# buck_connector-2.net
KiCad netlist of a schematic drawn in EAGLE
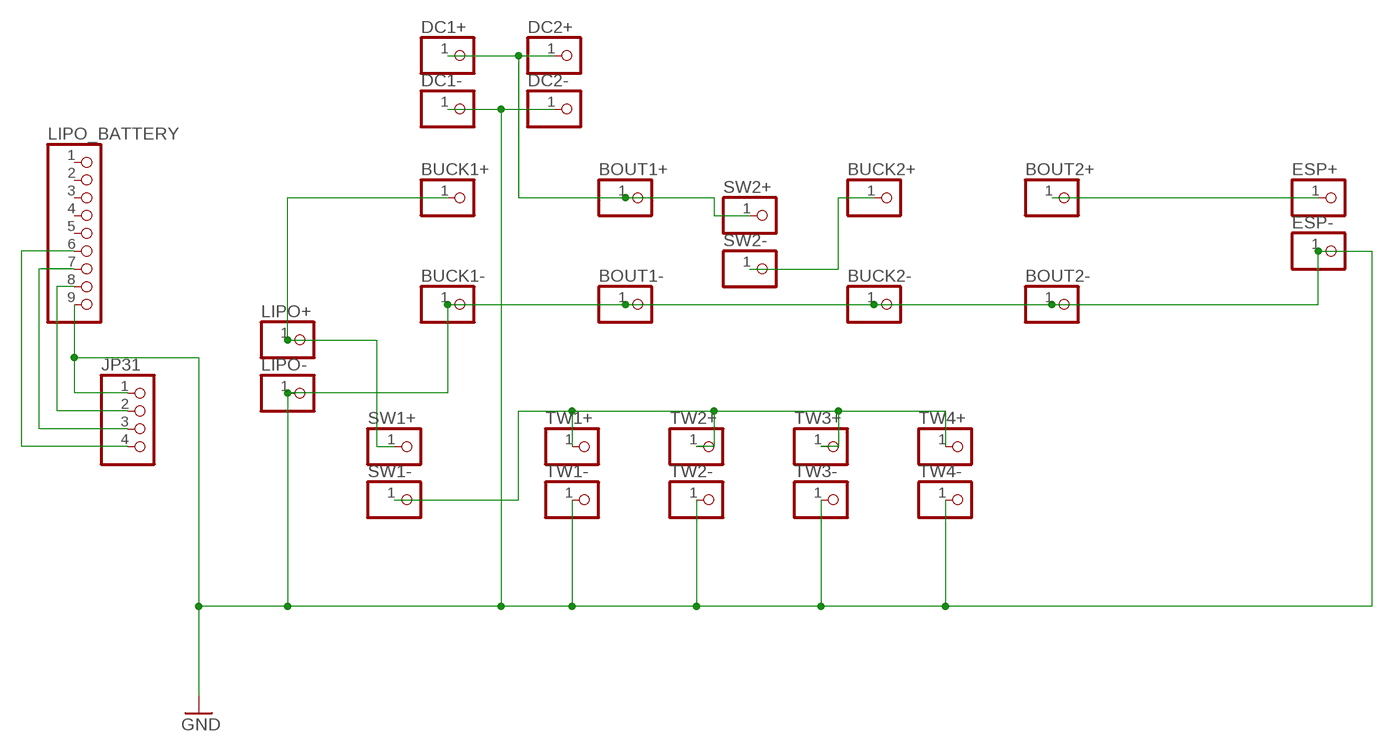
[diagram p0: schematic, sheet 1]

(export (version "E")
  (design (tool "Eeschema 10.0.6"))
  (components
    (comp (ref "BOUT1+")
      (value "PINHD-1X1")
      (footprint "eagle-import:1X01")
      (libsource (lib "eagle-import") (part "PINHD-1X1"))
    )
    (comp (ref "BOUT1-")
      (value "PINHD-1X1")
      (footprint "eagle-import:1X01")
      (libsource (lib "eagle-import") (part "PINHD-1X1"))
    )
    (comp (ref "BOUT2+")
      (value "PINHD-1X1")
      (footprint "eagle-import:1X01")
      (libsource (lib "eagle-import") (part "PINHD-1X1"))
    )
    (comp (ref "BOUT2-")
      (value "PINHD-1X1")
      (footprint "eagle-import:1X01")
      (libsource (lib "eagle-import") (part "PINHD-1X1"))
    )
    (comp (ref "BUCK1+")
      (value "PINHD-1X1")
      (footprint "eagle-import:1X01")
      (libsource (lib "eagle-import") (part "PINHD-1X1"))
    )
    (comp (ref "BUCK1-")
      (value "PINHD-1X1")
      (footprint "eagle-import:1X01")
      (libsource (lib "eagle-import") (part "PINHD-1X1"))
    )
    (comp (ref "BUCK2+")
      (value "PINHD-1X1")
      (footprint "eagle-import:1X01")
      (libsource (lib "eagle-import") (part "PINHD-1X1"))
    )
    (comp (ref "BUCK2-")
      (value "PINHD-1X1")
      (footprint "eagle-import:1X01")
      (libsource (lib "eagle-import") (part "PINHD-1X1"))
    )
    (comp (ref "DC1+")
      (value "PINHD-1X1")
      (footprint "eagle-import:1X01")
      (libsource (lib "eagle-import") (part "PINHD-1X1"))
    )
    (comp (ref "DC1-")
      (value "PINHD-1X1")
      (footprint "eagle-import:1X01")
      (libsource (lib "eagle-import") (part "PINHD-1X1"))
    )
    (comp (ref "DC2+")
      (value "PINHD-1X1")
      (footprint "eagle-import:1X01")
      (libsource (lib "eagle-import") (part "PINHD-1X1"))
    )
    (comp (ref "DC2-")
      (value "PINHD-1X1")
      (footprint "eagle-import:1X01")
      (libsource (lib "eagle-import") (part "PINHD-1X1"))
    )
    (comp (ref "ESP+")
      (value "PINHD-1X1")
      (footprint "eagle-import:1X01")
      (libsource (lib "eagle-import") (part "PINHD-1X1"))
    )
    (comp (ref "ESP-")
      (value "PINHD-1X1")
      (footprint "eagle-import:1X01")
      (libsource (lib "eagle-import") (part "PINHD-1X1"))
    )
    (comp (ref "JP31")
      (value "PINHD-1X4")
      (footprint "eagle-import:1X04")
      (libsource (lib "eagle-import") (part "PINHD-1X4"))
    )
    (comp (ref "LIPO+")
      (value "PINHD-1X1")
      (footprint "eagle-import:1X01")
      (libsource (lib "eagle-import") (part "PINHD-1X1"))
    )
    (comp (ref "LIPO-")
      (value "PINHD-1X1")
      (footprint "eagle-import:1X01")
      (libsource (lib "eagle-import") (part "PINHD-1X1"))
    )
    (comp (ref "LIPO_BATTERY")
      (value "PINHD-1X9")
      (footprint "eagle-import:1X09")
      (libsource (lib "eagle-import") (part "PINHD-1X9"))
    )
    (comp (ref "SW1+")
      (value "PINHD-1X1")
      (footprint "eagle-import:1X01")
      (libsource (lib "eagle-import") (part "PINHD-1X1"))
    )
    (comp (ref "SW1-")
      (value "PINHD-1X1")
      (footprint "eagle-import:1X01")
      (libsource (lib "eagle-import") (part "PINHD-1X1"))
    )
    (comp (ref "SW2+")
      (value "PINHD-1X1")
      (footprint "eagle-import:1X01")
      (libsource (lib "eagle-import") (part "PINHD-1X1"))
    )
    (comp (ref "SW2-")
      (value "PINHD-1X1")
      (footprint "eagle-import:1X01")
      (libsource (lib "eagle-import") (part "PINHD-1X1"))
    )
    (comp (ref "TW1+")
      (value "PINHD-1X1")
      (footprint "eagle-import:1X01")
      (libsource (lib "eagle-import") (part "PINHD-1X1"))
    )
    (comp (ref "TW1-")
      (value "PINHD-1X1")
      (footprint "eagle-import:1X01")
      (libsource (lib "eagle-import") (part "PINHD-1X1"))
    )
    (comp (ref "TW2+")
      (value "PINHD-1X1")
      (footprint "eagle-import:1X01")
      (libsource (lib "eagle-import") (part "PINHD-1X1"))
    )
    (comp (ref "TW2-")
      (value "PINHD-1X1")
      (footprint "eagle-import:1X01")
      (libsource (lib "eagle-import") (part "PINHD-1X1"))
    )
    (comp (ref "TW3+")
      (value "PINHD-1X1")
      (footprint "eagle-import:1X01")
      (libsource (lib "eagle-import") (part "PINHD-1X1"))
    )
    (comp (ref "TW3-")
      (value "PINHD-1X1")
      (footprint "eagle-import:1X01")
      (libsource (lib "eagle-import") (part "PINHD-1X1"))
    )
    (comp (ref "TW4+")
      (value "PINHD-1X1")
      (footprint "eagle-import:1X01")
      (libsource (lib "eagle-import") (part "PINHD-1X1"))
    )
    (comp (ref "TW4-")
      (value "PINHD-1X1")
      (footprint "eagle-import:1X01")
      (libsource (lib "eagle-import") (part "PINHD-1X1"))
    )
  )
  (nets
    (net (code "1") (name "GND") (class "Default")
      (node (ref "BOUT1-") (pin "1") (pinfunction "1_1") (pintype "passive"))
      (node (ref "BOUT2-") (pin "1") (pinfunction "1_1") (pintype "passive"))
      (node (ref "BUCK1-") (pin "1") (pinfunction "1_1") (pintype "passive"))
      (node (ref "BUCK2-") (pin "1") (pinfunction "1_1") (pintype "passive"))
      (node (ref "DC1-") (pin "1") (pinfunction "1_1") (pintype "passive"))
      (node (ref "DC2-") (pin "1") (pinfunction "1_1") (pintype "passive"))
      (node (ref "ESP-") (pin "1") (pinfunction "1_1") (pintype "passive"))
      (node (ref "JP31") (pin "1") (pinfunction "1_1") (pintype "passive"))
      (node (ref "LIPO-") (pin "1") (pinfunction "1_1") (pintype "passive"))
      (node (ref "LIPO_BATTERY") (pin "9") (pinfunction "9_9") (pintype "passive"))
      (node (ref "TW1-") (pin "1") (pinfunction "1_1") (pintype "passive"))
      (node (ref "TW2-") (pin "1") (pinfunction "1_1") (pintype "passive"))
      (node (ref "TW3-") (pin "1") (pinfunction "1_1") (pintype "passive"))
      (node (ref "TW4-") (pin "1") (pinfunction "1_1") (pintype "passive"))
    )
    (net (code "2") (name "Net-(BOUT1+-Pad1)") (class "Default")
      (node (ref "BOUT1+") (pin "1") (pinfunction "1_1") (pintype "passive"))
      (node (ref "DC1+") (pin "1") (pinfunction "1_1") (pintype "passive"))
      (node (ref "DC2+") (pin "1") (pinfunction "1_1") (pintype "passive"))
      (node (ref "SW2+") (pin "1") (pinfunction "1_1") (pintype "passive"))
    )
    (net (code "3") (name "Net-(BOUT2+-Pad1)") (class "Default")
      (node (ref "BOUT2+") (pin "1") (pinfunction "1_1") (pintype "passive"))
      (node (ref "ESP+") (pin "1") (pinfunction "1_1") (pintype "passive"))
    )
    (net (code "4") (name "Net-(BUCK1+-Pad1)") (class "Default")
      (node (ref "BUCK1+") (pin "1") (pinfunction "1_1") (pintype "passive"))
      (node (ref "LIPO+") (pin "1") (pinfunction "1_1") (pintype "passive"))
      (node (ref "SW1+") (pin "1") (pinfunction "1_1") (pintype "passive"))
    )
    (net (code "5") (name "Net-(BUCK2+-Pad1)") (class "Default")
      (node (ref "BUCK2+") (pin "1") (pinfunction "1_1") (pintype "passive"))
      (node (ref "SW2-") (pin "1") (pinfunction "1_1") (pintype "passive"))
    )
    (net (code "6") (name "Net-(JP31-Pad2)") (class "Default")
      (node (ref "JP31") (pin "2") (pinfunction "2_2") (pintype "passive"))
      (node (ref "LIPO_BATTERY") (pin "8") (pinfunction "8_8") (pintype "passive"))
    )
    (net (code "7") (name "Net-(JP31-Pad3)") (class "Default")
      (node (ref "JP31") (pin "3") (pinfunction "3_3") (pintype "passive"))
      (node (ref "LIPO_BATTERY") (pin "7") (pinfunction "7_7") (pintype "passive"))
    )
    (net (code "8") (name "Net-(JP31-Pad4)") (class "Default")
      (node (ref "JP31") (pin "4") (pinfunction "4_4") (pintype "passive"))
      (node (ref "LIPO_BATTERY") (pin "6") (pinfunction "6_6") (pintype "passive"))
    )
    (net (code "9") (name "Net-(SW1--Pad1)") (class "Default")
      (node (ref "SW1-") (pin "1") (pinfunction "1_1") (pintype "passive"))
      (node (ref "TW1+") (pin "1") (pinfunction "1_1") (pintype "passive"))
      (node (ref "TW2+") (pin "1") (pinfunction "1_1") (pintype "passive"))
      (node (ref "TW3+") (pin "1") (pinfunction "1_1") (pintype "passive"))
      (node (ref "TW4+") (pin "1") (pinfunction "1_1") (pintype "passive"))
    )
    (net (code "10") (name "unconnected-(LIPO_BATTERY-Pad1)") (class "Default")
      (node (ref "LIPO_BATTERY") (pin "1") (pinfunction "1_1") (pintype "passive"))
    )
    (net (code "11") (name "unconnected-(LIPO_BATTERY-Pad2)") (class "Default")
      (node (ref "LIPO_BATTERY") (pin "2") (pinfunction "2_2") (pintype "passive"))
    )
    (net (code "12") (name "unconnected-(LIPO_BATTERY-Pad3)") (class "Default")
      (node (ref "LIPO_BATTERY") (pin "3") (pinfunction "3_3") (pintype "passive"))
    )
    (net (code "13") (name "unconnected-(LIPO_BATTERY-Pad4)") (class "Default")
      (node (ref "LIPO_BATTERY") (pin "4") (pinfunction "4_4") (pintype "passive"))
    )
    (net (code "14") (name "unconnected-(LIPO_BATTERY-Pad5)") (class "Default")
      (node (ref "LIPO_BATTERY") (pin "5") (pinfunction "5_5") (pintype "passive"))
    )
  )
)
